# R_hren.net
KiCad netlist of a schematic drawn in EAGLE
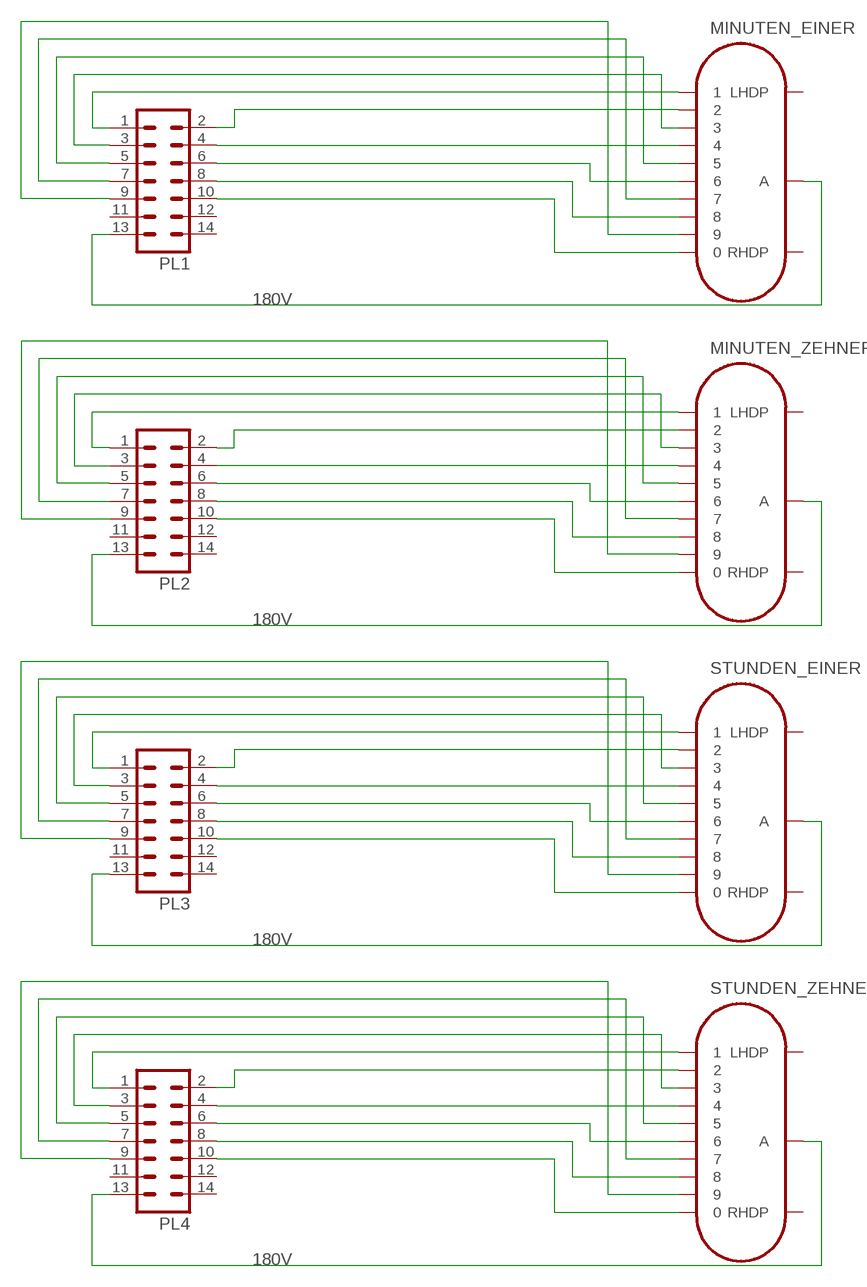
[diagram p0: schematic, sheet 1]

(export (version "E")
  (design (tool "Eeschema 10.0.6"))
  (components
    (comp (ref "MINUTEN_EINER")
      (value "IN-16")
      (footprint "eagle-import:IN-16")
      (libsource (lib "eagle-import") (part "IN-16"))
    )
    (comp (ref "MINUTEN_ZEHNER")
      (value "IN-16")
      (footprint "eagle-import:IN-16")
      (libsource (lib "eagle-import") (part "IN-16"))
    )
    (comp (ref "PL1")
      (value "ML14")
      (footprint "eagle-import:ML14")
      (libsource (lib "eagle-import") (part "ML14"))
    )
    (comp (ref "PL2")
      (value "ML14")
      (footprint "eagle-import:ML14")
      (libsource (lib "eagle-import") (part "ML14"))
    )
    (comp (ref "PL3")
      (value "ML14")
      (footprint "eagle-import:ML14")
      (libsource (lib "eagle-import") (part "ML14"))
    )
    (comp (ref "PL4")
      (value "ML14")
      (footprint "eagle-import:ML14")
      (libsource (lib "eagle-import") (part "ML14"))
    )
    (comp (ref "STUNDEN_EINER")
      (value "IN-16")
      (footprint "eagle-import:IN-16")
      (libsource (lib "eagle-import") (part "IN-16"))
    )
    (comp (ref "STUNDEN_ZEHNER")
      (value "IN-16")
      (footprint "eagle-import:IN-16")
      (libsource (lib "eagle-import") (part "IN-16"))
    )
  )
  (nets
    (net (code "1") (name "Net-(MINUTEN_EINER-Pad0)") (class "Default")
      (node (ref "MINUTEN_EINER") (pin "0") (pinfunction "0_0") (pintype "bidirectional"))
      (node (ref "PL1") (pin "10") (pinfunction "10_10") (pintype "passive"))
    )
    (net (code "2") (name "Net-(MINUTEN_EINER-Pad1)") (class "Default")
      (node (ref "MINUTEN_EINER") (pin "1") (pinfunction "1_1") (pintype "bidirectional"))
      (node (ref "PL1") (pin "1") (pinfunction "1_1") (pintype "passive"))
    )
    (net (code "3") (name "Net-(MINUTEN_EINER-Pad2)") (class "Default")
      (node (ref "MINUTEN_EINER") (pin "2") (pinfunction "2_2") (pintype "bidirectional"))
      (node (ref "PL1") (pin "2") (pinfunction "2_2") (pintype "passive"))
    )
    (net (code "4") (name "Net-(MINUTEN_EINER-Pad3)") (class "Default")
      (node (ref "MINUTEN_EINER") (pin "3") (pinfunction "3_3") (pintype "bidirectional"))
      (node (ref "PL1") (pin "3") (pinfunction "3_3") (pintype "passive"))
    )
    (net (code "5") (name "Net-(MINUTEN_EINER-Pad4)") (class "Default")
      (node (ref "MINUTEN_EINER") (pin "4") (pinfunction "4_4") (pintype "bidirectional"))
      (node (ref "PL1") (pin "4") (pinfunction "4_4") (pintype "passive"))
    )
    (net (code "6") (name "Net-(MINUTEN_EINER-Pad5)") (class "Default")
      (node (ref "MINUTEN_EINER") (pin "5") (pinfunction "5_5") (pintype "bidirectional"))
      (node (ref "PL1") (pin "5") (pinfunction "5_5") (pintype "passive"))
    )
    (net (code "7") (name "Net-(MINUTEN_EINER-Pad6)") (class "Default")
      (node (ref "MINUTEN_EINER") (pin "6") (pinfunction "6_6") (pintype "bidirectional"))
      (node (ref "PL1") (pin "6") (pinfunction "6_6") (pintype "passive"))
    )
    (net (code "8") (name "Net-(MINUTEN_EINER-Pad7)") (class "Default")
      (node (ref "MINUTEN_EINER") (pin "7") (pinfunction "7_7") (pintype "bidirectional"))
      (node (ref "PL1") (pin "7") (pinfunction "7_7") (pintype "passive"))
    )
    (net (code "9") (name "Net-(MINUTEN_EINER-Pad8)") (class "Default")
      (node (ref "MINUTEN_EINER") (pin "8") (pinfunction "8_8") (pintype "bidirectional"))
      (node (ref "PL1") (pin "8") (pinfunction "8_8") (pintype "passive"))
    )
    (net (code "10") (name "Net-(MINUTEN_EINER-Pad9)") (class "Default")
      (node (ref "MINUTEN_EINER") (pin "9") (pinfunction "9_9") (pintype "bidirectional"))
      (node (ref "PL1") (pin "9") (pinfunction "9_9") (pintype "passive"))
    )
    (net (code "11") (name "Net-(MINUTEN_EINER-PadA)") (class "Default")
      (node (ref "MINUTEN_EINER") (pin "A") (pinfunction "A_A") (pintype "bidirectional"))
      (node (ref "PL1") (pin "13") (pinfunction "13_13") (pintype "passive"))
    )
    (net (code "12") (name "Net-(MINUTEN_ZEHNER-Pad0)") (class "Default")
      (node (ref "MINUTEN_ZEHNER") (pin "0") (pinfunction "0_0") (pintype "bidirectional"))
      (node (ref "PL2") (pin "10") (pinfunction "10_10") (pintype "passive"))
    )
    (net (code "13") (name "Net-(MINUTEN_ZEHNER-Pad1)") (class "Default")
      (node (ref "MINUTEN_ZEHNER") (pin "1") (pinfunction "1_1") (pintype "bidirectional"))
      (node (ref "PL2") (pin "1") (pinfunction "1_1") (pintype "passive"))
    )
    (net (code "14") (name "Net-(MINUTEN_ZEHNER-Pad2)") (class "Default")
      (node (ref "MINUTEN_ZEHNER") (pin "2") (pinfunction "2_2") (pintype "bidirectional"))
      (node (ref "PL2") (pin "2") (pinfunction "2_2") (pintype "passive"))
    )
    (net (code "15") (name "Net-(MINUTEN_ZEHNER-Pad3)") (class "Default")
      (node (ref "MINUTEN_ZEHNER") (pin "3") (pinfunction "3_3") (pintype "bidirectional"))
      (node (ref "PL2") (pin "3") (pinfunction "3_3") (pintype "passive"))
    )
    (net (code "16") (name "Net-(MINUTEN_ZEHNER-Pad4)") (class "Default")
      (node (ref "MINUTEN_ZEHNER") (pin "4") (pinfunction "4_4") (pintype "bidirectional"))
      (node (ref "PL2") (pin "4") (pinfunction "4_4") (pintype "passive"))
    )
    (net (code "17") (name "Net-(MINUTEN_ZEHNER-Pad5)") (class "Default")
      (node (ref "MINUTEN_ZEHNER") (pin "5") (pinfunction "5_5") (pintype "bidirectional"))
      (node (ref "PL2") (pin "5") (pinfunction "5_5") (pintype "passive"))
    )
    (net (code "18") (name "Net-(MINUTEN_ZEHNER-Pad6)") (class "Default")
      (node (ref "MINUTEN_ZEHNER") (pin "6") (pinfunction "6_6") (pintype "bidirectional"))
      (node (ref "PL2") (pin "6") (pinfunction "6_6") (pintype "passive"))
    )
    (net (code "19") (name "Net-(MINUTEN_ZEHNER-Pad7)") (class "Default")
      (node (ref "MINUTEN_ZEHNER") (pin "7") (pinfunction "7_7") (pintype "bidirectional"))
      (node (ref "PL2") (pin "7") (pinfunction "7_7") (pintype "passive"))
    )
    (net (code "20") (name "Net-(MINUTEN_ZEHNER-Pad8)") (class "Default")
      (node (ref "MINUTEN_ZEHNER") (pin "8") (pinfunction "8_8") (pintype "bidirectional"))
      (node (ref "PL2") (pin "8") (pinfunction "8_8") (pintype "passive"))
    )
    (net (code "21") (name "Net-(MINUTEN_ZEHNER-Pad9)") (class "Default")
      (node (ref "MINUTEN_ZEHNER") (pin "9") (pinfunction "9_9") (pintype "bidirectional"))
      (node (ref "PL2") (pin "9") (pinfunction "9_9") (pintype "passive"))
    )
    (net (code "22") (name "Net-(MINUTEN_ZEHNER-PadA)") (class "Default")
      (node (ref "MINUTEN_ZEHNER") (pin "A") (pinfunction "A_A") (pintype "bidirectional"))
      (node (ref "PL2") (pin "13") (pinfunction "13_13") (pintype "passive"))
    )
    (net (code "23") (name "Net-(PL3-Pad1)") (class "Default")
      (node (ref "PL3") (pin "1") (pinfunction "1_1") (pintype "passive"))
      (node (ref "STUNDEN_EINER") (pin "1") (pinfunction "1_1") (pintype "bidirectional"))
    )
    (net (code "24") (name "Net-(PL3-Pad2)") (class "Default")
      (node (ref "PL3") (pin "2") (pinfunction "2_2") (pintype "passive"))
      (node (ref "STUNDEN_EINER") (pin "2") (pinfunction "2_2") (pintype "bidirectional"))
    )
    (net (code "25") (name "Net-(PL3-Pad3)") (class "Default")
      (node (ref "PL3") (pin "3") (pinfunction "3_3") (pintype "passive"))
      (node (ref "STUNDEN_EINER") (pin "3") (pinfunction "3_3") (pintype "bidirectional"))
    )
    (net (code "26") (name "Net-(PL3-Pad4)") (class "Default")
      (node (ref "PL3") (pin "4") (pinfunction "4_4") (pintype "passive"))
      (node (ref "STUNDEN_EINER") (pin "4") (pinfunction "4_4") (pintype "bidirectional"))
    )
    (net (code "27") (name "Net-(PL3-Pad5)") (class "Default")
      (node (ref "PL3") (pin "5") (pinfunction "5_5") (pintype "passive"))
      (node (ref "STUNDEN_EINER") (pin "5") (pinfunction "5_5") (pintype "bidirectional"))
    )
    (net (code "28") (name "Net-(PL3-Pad6)") (class "Default")
      (node (ref "PL3") (pin "6") (pinfunction "6_6") (pintype "passive"))
      (node (ref "STUNDEN_EINER") (pin "6") (pinfunction "6_6") (pintype "bidirectional"))
    )
    (net (code "29") (name "Net-(PL3-Pad7)") (class "Default")
      (node (ref "PL3") (pin "7") (pinfunction "7_7") (pintype "passive"))
      (node (ref "STUNDEN_EINER") (pin "7") (pinfunction "7_7") (pintype "bidirectional"))
    )
    (net (code "30") (name "Net-(PL3-Pad8)") (class "Default")
      (node (ref "PL3") (pin "8") (pinfunction "8_8") (pintype "passive"))
      (node (ref "STUNDEN_EINER") (pin "8") (pinfunction "8_8") (pintype "bidirectional"))
    )
    (net (code "31") (name "Net-(PL3-Pad9)") (class "Default")
      (node (ref "PL3") (pin "9") (pinfunction "9_9") (pintype "passive"))
      (node (ref "STUNDEN_EINER") (pin "9") (pinfunction "9_9") (pintype "bidirectional"))
    )
    (net (code "32") (name "Net-(PL3-Pad10)") (class "Default")
      (node (ref "PL3") (pin "10") (pinfunction "10_10") (pintype "passive"))
      (node (ref "STUNDEN_EINER") (pin "0") (pinfunction "0_0") (pintype "bidirectional"))
    )
    (net (code "33") (name "Net-(PL3-Pad13)") (class "Default")
      (node (ref "PL3") (pin "13") (pinfunction "13_13") (pintype "passive"))
      (node (ref "STUNDEN_EINER") (pin "A") (pinfunction "A_A") (pintype "bidirectional"))
    )
    (net (code "34") (name "Net-(PL4-Pad1)") (class "Default")
      (node (ref "PL4") (pin "1") (pinfunction "1_1") (pintype "passive"))
      (node (ref "STUNDEN_ZEHNER") (pin "1") (pinfunction "1_1") (pintype "bidirectional"))
    )
    (net (code "35") (name "Net-(PL4-Pad2)") (class "Default")
      (node (ref "PL4") (pin "2") (pinfunction "2_2") (pintype "passive"))
      (node (ref "STUNDEN_ZEHNER") (pin "2") (pinfunction "2_2") (pintype "bidirectional"))
    )
    (net (code "36") (name "Net-(PL4-Pad3)") (class "Default")
      (node (ref "PL4") (pin "3") (pinfunction "3_3") (pintype "passive"))
      (node (ref "STUNDEN_ZEHNER") (pin "3") (pinfunction "3_3") (pintype "bidirectional"))
    )
    (net (code "37") (name "Net-(PL4-Pad4)") (class "Default")
      (node (ref "PL4") (pin "4") (pinfunction "4_4") (pintype "passive"))
      (node (ref "STUNDEN_ZEHNER") (pin "4") (pinfunction "4_4") (pintype "bidirectional"))
    )
    (net (code "38") (name "Net-(PL4-Pad5)") (class "Default")
      (node (ref "PL4") (pin "5") (pinfunction "5_5") (pintype "passive"))
      (node (ref "STUNDEN_ZEHNER") (pin "5") (pinfunction "5_5") (pintype "bidirectional"))
    )
    (net (code "39") (name "Net-(PL4-Pad6)") (class "Default")
      (node (ref "PL4") (pin "6") (pinfunction "6_6") (pintype "passive"))
      (node (ref "STUNDEN_ZEHNER") (pin "6") (pinfunction "6_6") (pintype "bidirectional"))
    )
    (net (code "40") (name "Net-(PL4-Pad7)") (class "Default")
      (node (ref "PL4") (pin "7") (pinfunction "7_7") (pintype "passive"))
      (node (ref "STUNDEN_ZEHNER") (pin "7") (pinfunction "7_7") (pintype "bidirectional"))
    )
    (net (code "41") (name "Net-(PL4-Pad8)") (class "Default")
      (node (ref "PL4") (pin "8") (pinfunction "8_8") (pintype "passive"))
      (node (ref "STUNDEN_ZEHNER") (pin "8") (pinfunction "8_8") (pintype "bidirectional"))
    )
    (net (code "42") (name "Net-(PL4-Pad9)") (class "Default")
      (node (ref "PL4") (pin "9") (pinfunction "9_9") (pintype "passive"))
      (node (ref "STUNDEN_ZEHNER") (pin "9") (pinfunction "9_9") (pintype "bidirectional"))
    )
    (net (code "43") (name "Net-(PL4-Pad10)") (class "Default")
      (node (ref "PL4") (pin "10") (pinfunction "10_10") (pintype "passive"))
      (node (ref "STUNDEN_ZEHNER") (pin "0") (pinfunction "0_0") (pintype "bidirectional"))
    )
    (net (code "44") (name "Net-(PL4-Pad13)") (class "Default")
      (node (ref "PL4") (pin "13") (pinfunction "13_13") (pintype "passive"))
      (node (ref "STUNDEN_ZEHNER") (pin "A") (pinfunction "A_A") (pintype "bidirectional"))
    )
    (net (code "45") (name "unconnected-(MINUTEN_EINER-PadLHDP)") (class "Default")
      (node (ref "MINUTEN_EINER") (pin "LHDP") (pinfunction "LHDP_LHDP") (pintype "bidirectional"))
    )
    (net (code "46") (name "unconnected-(MINUTEN_EINER-PadRHDP)") (class "Default")
      (node (ref "MINUTEN_EINER") (pin "RHDP") (pinfunction "RHDP_RHDP") (pintype "bidirectional"))
    )
    (net (code "47") (name "unconnected-(MINUTEN_ZEHNER-PadLHDP)") (class "Default")
      (node (ref "MINUTEN_ZEHNER") (pin "LHDP") (pinfunction "LHDP_LHDP") (pintype "bidirectional"))
    )
    (net (code "48") (name "unconnected-(MINUTEN_ZEHNER-PadRHDP)") (class "Default")
      (node (ref "MINUTEN_ZEHNER") (pin "RHDP") (pinfunction "RHDP_RHDP") (pintype "bidirectional"))
    )
    (net (code "49") (name "unconnected-(PL1-Pad11)") (class "Default")
      (node (ref "PL1") (pin "11") (pinfunction "11_11") (pintype "passive"))
    )
    (net (code "50") (name "unconnected-(PL1-Pad12)") (class "Default")
      (node (ref "PL1") (pin "12") (pinfunction "12_12") (pintype "passive"))
    )
    (net (code "51") (name "unconnected-(PL1-Pad14)") (class "Default")
      (node (ref "PL1") (pin "14") (pinfunction "14_14") (pintype "passive"))
    )
    (net (code "52") (name "unconnected-(PL2-Pad11)") (class "Default")
      (node (ref "PL2") (pin "11") (pinfunction "11_11") (pintype "passive"))
    )
    (net (code "53") (name "unconnected-(PL2-Pad12)") (class "Default")
      (node (ref "PL2") (pin "12") (pinfunction "12_12") (pintype "passive"))
    )
    (net (code "54") (name "unconnected-(PL2-Pad14)") (class "Default")
      (node (ref "PL2") (pin "14") (pinfunction "14_14") (pintype "passive"))
    )
    (net (code "55") (name "unconnected-(PL3-Pad11)") (class "Default")
      (node (ref "PL3") (pin "11") (pinfunction "11_11") (pintype "passive"))
    )
    (net (code "56") (name "unconnected-(PL3-Pad12)") (class "Default")
      (node (ref "PL3") (pin "12") (pinfunction "12_12") (pintype "passive"))
    )
    (net (code "57") (name "unconnected-(PL3-Pad14)") (class "Default")
      (node (ref "PL3") (pin "14") (pinfunction "14_14") (pintype "passive"))
    )
    (net (code "58") (name "unconnected-(PL4-Pad11)") (class "Default")
      (node (ref "PL4") (pin "11") (pinfunction "11_11") (pintype "passive"))
    )
    (net (code "59") (name "unconnected-(PL4-Pad12)") (class "Default")
      (node (ref "PL4") (pin "12") (pinfunction "12_12") (pintype "passive"))
    )
    (net (code "60") (name "unconnected-(PL4-Pad14)") (class "Default")
      (node (ref "PL4") (pin "14") (pinfunction "14_14") (pintype "passive"))
    )
    (net (code "61") (name "unconnected-(STUNDEN_EINER-PadLHDP)") (class "Default")
      (node (ref "STUNDEN_EINER") (pin "LHDP") (pinfunction "LHDP_LHDP") (pintype "bidirectional"))
    )
    (net (code "62") (name "unconnected-(STUNDEN_EINER-PadRHDP)") (class "Default")
      (node (ref "STUNDEN_EINER") (pin "RHDP") (pinfunction "RHDP_RHDP") (pintype "bidirectional"))
    )
    (net (code "63") (name "unconnected-(STUNDEN_ZEHNER-PadLHDP)") (class "Default")
      (node (ref "STUNDEN_ZEHNER") (pin "LHDP") (pinfunction "LHDP_LHDP") (pintype "bidirectional"))
    )
    (net (code "64") (name "unconnected-(STUNDEN_ZEHNER-PadRHDP)") (class "Default")
      (node (ref "STUNDEN_ZEHNER") (pin "RHDP") (pinfunction "RHDP_RHDP") (pintype "bidirectional"))
    )
  )
)
